# 16-BitSW.net
KiCad netlist of a schematic drawn in Altium Designer
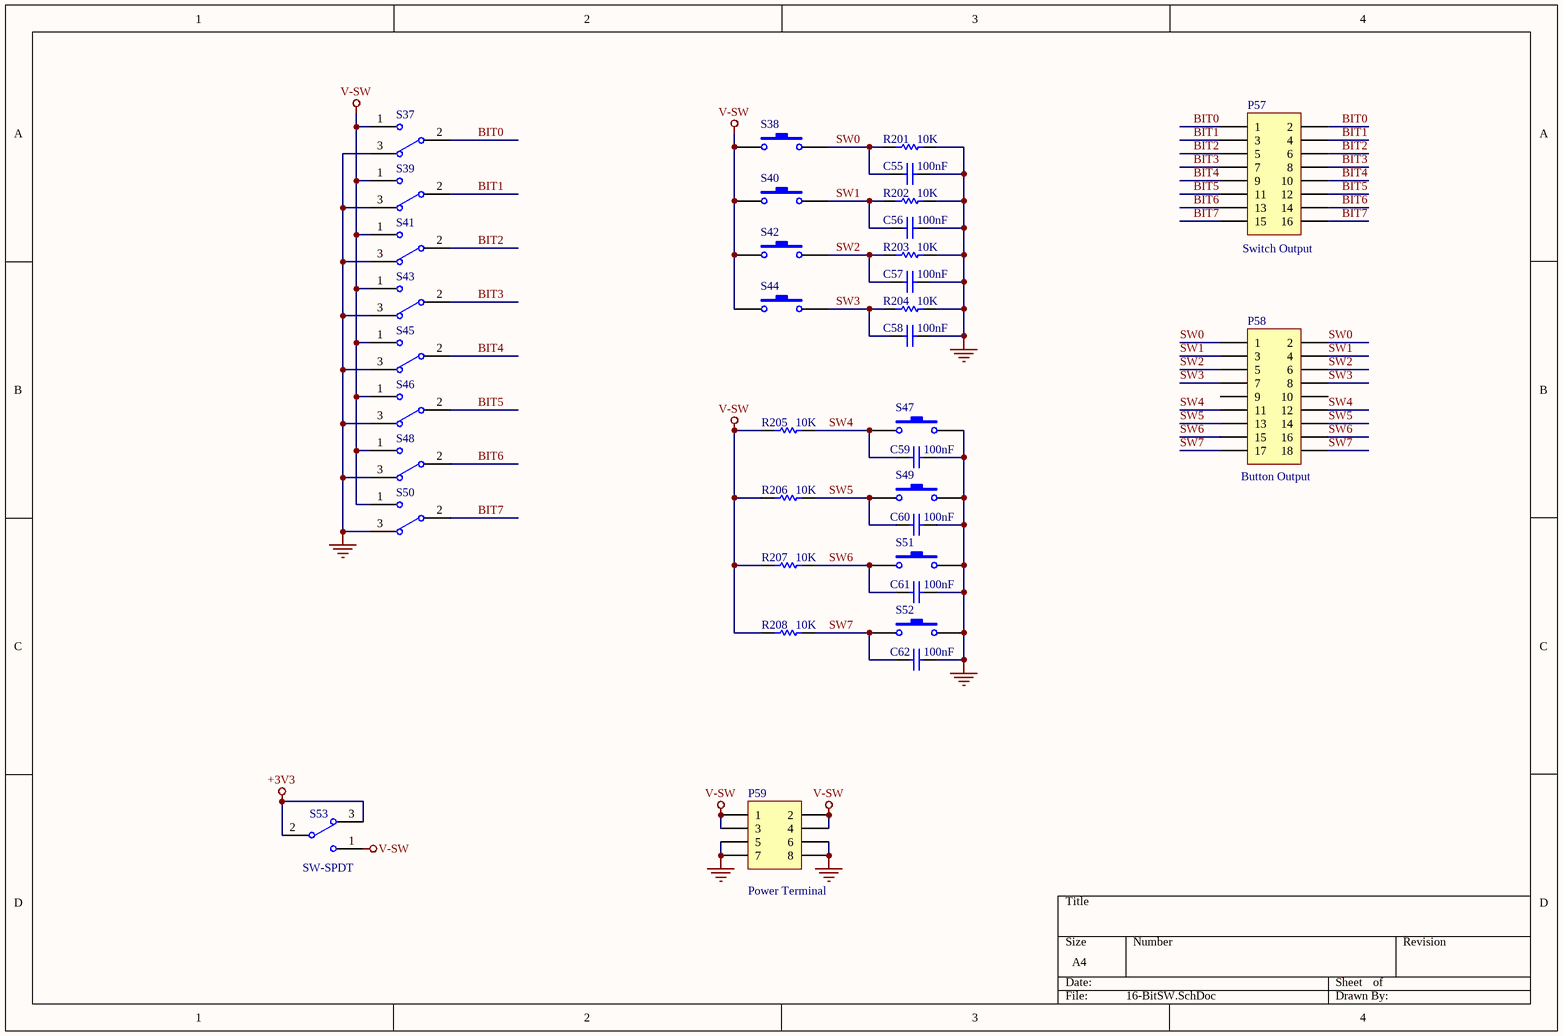
[diagram p0: 16-BitSW.SchDoc]

(export (version "E")
  (design (tool "Eeschema 10.0.6"))
  (components
    (comp (ref "C55")
      (value "100nF")
      (footprint "C-0805")
      (description "Capacitor")
      (fields
        (field (name "MANUFACTURER") "Generic Components")
        (field (name "Comment") "104")
        (field (name "PUBLISHER") "Altium Hobart Technology Centre")
      )
      (libsource (lib "Miscellaneous Devices") (part "Cap"))
    )
    (comp (ref "C56")
      (value "100nF")
      (footprint "C-0805")
      (description "Capacitor")
      (fields
        (field (name "MANUFACTURER") "Generic Components")
        (field (name "Comment") "104")
        (field (name "PUBLISHER") "Altium Hobart Technology Centre")
      )
      (libsource (lib "Miscellaneous Devices") (part "Cap"))
    )
    (comp (ref "C57")
      (value "100nF")
      (footprint "C-0805")
      (description "Capacitor")
      (fields
        (field (name "MANUFACTURER") "Generic Components")
        (field (name "Comment") "104")
        (field (name "PUBLISHER") "Altium Hobart Technology Centre")
      )
      (libsource (lib "Miscellaneous Devices") (part "Cap"))
    )
    (comp (ref "C58")
      (value "100nF")
      (footprint "C-0805")
      (description "Capacitor")
      (fields
        (field (name "MANUFACTURER") "Generic Components")
        (field (name "Comment") "104")
        (field (name "PUBLISHER") "Altium Hobart Technology Centre")
      )
      (libsource (lib "Miscellaneous Devices") (part "Cap"))
    )
    (comp (ref "C59")
      (value "100nF")
      (footprint "C-0805")
      (description "Capacitor")
      (fields
        (field (name "MANUFACTURER") "Generic Components")
        (field (name "Comment") "104")
        (field (name "PUBLISHER") "Altium Hobart Technology Centre")
      )
      (libsource (lib "Miscellaneous Devices") (part "Cap"))
    )
    (comp (ref "C60")
      (value "100nF")
      (footprint "C-0805")
      (description "Capacitor")
      (fields
        (field (name "MANUFACTURER") "Generic Components")
        (field (name "Comment") "104")
        (field (name "PUBLISHER") "Altium Hobart Technology Centre")
      )
      (libsource (lib "Miscellaneous Devices") (part "Cap"))
    )
    (comp (ref "C61")
      (value "100nF")
      (footprint "C-0805")
      (description "Capacitor")
      (fields
        (field (name "MANUFACTURER") "Generic Components")
        (field (name "Comment") "104")
        (field (name "PUBLISHER") "Altium Hobart Technology Centre")
      )
      (libsource (lib "Miscellaneous Devices") (part "Cap"))
    )
    (comp (ref "C62")
      (value "100nF")
      (footprint "C-0805")
      (description "Capacitor")
      (fields
        (field (name "MANUFACTURER") "Generic Components")
        (field (name "Comment") "104")
        (field (name "PUBLISHER") "Altium Hobart Technology Centre")
      )
      (libsource (lib "Miscellaneous Devices") (part "Cap"))
    )
    (comp (ref "P57")
      (value "Switch Output")
      (footprint "HDR2X8")
      (description "Header, 8-Pin, Dual row")
      (fields (field (name "Comment") "Header 8X2"))
      (libsource (lib "Miscellaneous Connectors") (part "Header 8X2"))
    )
    (comp (ref "P58")
      (value "Button Output")
      (footprint "HDR2X9")
      (description "Header, 9-Pin, Dual row")
      (fields (field (name "Comment") "Header 9X2"))
      (libsource (lib "Miscellaneous Connectors") (part "Header 9X2"))
    )
    (comp (ref "P59")
      (value "Header 4X2")
      (footprint "HDR2X4")
      (description "Header, 4-Pin, Dual row")
      (fields (field (name "PUBLISHER") "Power Terminal"))
      (libsource (lib "Miscellaneous Connectors") (part "Header 4X2"))
    )
    (comp (ref "R201")
      (value "10K")
      (footprint "r-0805")
      (description "Resistor")
      (fields (field (name "PUBLISHER") "Altium Limited"))
      (libsource (lib "Miscellaneous Devices") (part "Res1"))
    )
    (comp (ref "R202")
      (value "10K")
      (footprint "r-0805")
      (description "Resistor")
      (fields (field (name "PUBLISHER") "Altium Limited"))
      (libsource (lib "Miscellaneous Devices") (part "Res1"))
    )
    (comp (ref "R203")
      (value "10K")
      (footprint "r-0805")
      (description "Resistor")
      (fields (field (name "PUBLISHER") "Altium Limited"))
      (libsource (lib "Miscellaneous Devices") (part "Res1"))
    )
    (comp (ref "R204")
      (value "10K")
      (footprint "r-0805")
      (description "Resistor")
      (fields (field (name "PUBLISHER") "Altium Limited"))
      (libsource (lib "Miscellaneous Devices") (part "Res1"))
    )
    (comp (ref "R205")
      (value "10K")
      (footprint "r-0805")
      (description "Resistor")
      (fields (field (name "PUBLISHER") "Altium Limited"))
      (libsource (lib "Miscellaneous Devices") (part "Res1"))
    )
    (comp (ref "R206")
      (value "10K")
      (footprint "r-0805")
      (description "Resistor")
      (fields (field (name "PUBLISHER") "Altium Limited"))
      (libsource (lib "Miscellaneous Devices") (part "Res1"))
    )
    (comp (ref "R207")
      (value "10K")
      (footprint "r-0805")
      (description "Resistor")
      (fields (field (name "PUBLISHER") "Altium Limited"))
      (libsource (lib "Miscellaneous Devices") (part "Res1"))
    )
    (comp (ref "R208")
      (value "10K")
      (footprint "r-0805")
      (description "Resistor")
      (fields (field (name "PUBLISHER") "Altium Limited"))
      (libsource (lib "Miscellaneous Devices") (part "Res1"))
    )
    (comp (ref "S37")
      (value "SW-SPDT")
      (footprint "SW-DIP1SMD")
      (description "SPDT Subminiature Toggle Switch, Right Angle Mounting, Vertical Actuation")
      (fields (field (name "PUBLISHER") "Altium Limited"))
      (libsource (lib "Miscellaneous Devices") (part "SW-SPDT"))
    )
    (comp (ref "S38")
      (value "SW2")
      (footprint "sw2")
      (description "Switch")
      (fields (field (name "PUBLISHER") "Altium Limited"))
      (libsource (lib "Miscellaneous Devices") (part "SW-PB"))
    )
    (comp (ref "S39")
      (value "SW-SPDT")
      (footprint "SW-DIP1SMD")
      (description "SPDT Subminiature Toggle Switch, Right Angle Mounting, Vertical Actuation")
      (fields (field (name "PUBLISHER") "Altium Limited"))
      (libsource (lib "Miscellaneous Devices") (part "SW-SPDT"))
    )
    (comp (ref "S40")
      (value "SW2")
      (footprint "sw2")
      (description "Switch")
      (fields (field (name "PUBLISHER") "Altium Limited"))
      (libsource (lib "Miscellaneous Devices") (part "SW-PB"))
    )
    (comp (ref "S41")
      (value "SW-SPDT")
      (footprint "SW-DIP1SMD")
      (description "SPDT Subminiature Toggle Switch, Right Angle Mounting, Vertical Actuation")
      (fields (field (name "PUBLISHER") "Altium Limited"))
      (libsource (lib "Miscellaneous Devices") (part "SW-SPDT"))
    )
    (comp (ref "S42")
      (value "SW2")
      (footprint "sw2")
      (description "Switch")
      (fields (field (name "PUBLISHER") "Altium Limited"))
      (libsource (lib "Miscellaneous Devices") (part "SW-PB"))
    )
    (comp (ref "S43")
      (value "SW-SPDT")
      (footprint "SW-DIP1SMD")
      (description "SPDT Subminiature Toggle Switch, Right Angle Mounting, Vertical Actuation")
      (fields (field (name "PUBLISHER") "Altium Limited"))
      (libsource (lib "Miscellaneous Devices") (part "SW-SPDT"))
    )
    (comp (ref "S44")
      (value "SW2")
      (footprint "sw2")
      (description "Switch")
      (fields (field (name "PUBLISHER") "Altium Limited"))
      (libsource (lib "Miscellaneous Devices") (part "SW-PB"))
    )
    (comp (ref "S45")
      (value "SW-SPDT")
      (footprint "SW-DIP1SMD")
      (description "SPDT Subminiature Toggle Switch, Right Angle Mounting, Vertical Actuation")
      (fields (field (name "PUBLISHER") "Altium Limited"))
      (libsource (lib "Miscellaneous Devices") (part "SW-SPDT"))
    )
    (comp (ref "S46")
      (value "SW-SPDT")
      (footprint "SW-DIP1SMD")
      (description "SPDT Subminiature Toggle Switch, Right Angle Mounting, Vertical Actuation")
      (fields (field (name "PUBLISHER") "Altium Limited"))
      (libsource (lib "Miscellaneous Devices") (part "SW-SPDT"))
    )
    (comp (ref "S47")
      (value "SW2")
      (footprint "sw2")
      (description "Switch")
      (fields (field (name "PUBLISHER") "Altium Limited"))
      (libsource (lib "Miscellaneous Devices") (part "SW-PB"))
    )
    (comp (ref "S48")
      (value "SW-SPDT")
      (footprint "SW-DIP1SMD")
      (description "SPDT Subminiature Toggle Switch, Right Angle Mounting, Vertical Actuation")
      (fields (field (name "PUBLISHER") "Altium Limited"))
      (libsource (lib "Miscellaneous Devices") (part "SW-SPDT"))
    )
    (comp (ref "S49")
      (value "SW2")
      (footprint "sw2")
      (description "Switch")
      (fields (field (name "PUBLISHER") "Altium Limited"))
      (libsource (lib "Miscellaneous Devices") (part "SW-PB"))
    )
    (comp (ref "S50")
      (value "SW-SPDT")
      (footprint "SW-DIP1SMD")
      (description "SPDT Subminiature Toggle Switch, Right Angle Mounting, Vertical Actuation")
      (fields (field (name "PUBLISHER") "Altium Limited"))
      (libsource (lib "Miscellaneous Devices") (part "SW-SPDT"))
    )
    (comp (ref "S51")
      (value "SW2")
      (footprint "sw2")
      (description "Switch")
      (fields (field (name "PUBLISHER") "Altium Limited"))
      (libsource (lib "Miscellaneous Devices") (part "SW-PB"))
    )
    (comp (ref "S52")
      (value "SW2")
      (footprint "sw2")
      (description "Switch")
      (fields (field (name "PUBLISHER") "Altium Limited"))
      (libsource (lib "Miscellaneous Devices") (part "SW-PB"))
    )
    (comp (ref "S53")
      (value "SW-SPDT")
      (footprint "SW-DIP1SMD")
      (description "SPDT Subminiature Toggle Switch, Right Angle Mounting, Vertical Actuation")
      (fields (field (name "PUBLISHER") "Altium Limited"))
      (libsource (lib "Miscellaneous Devices") (part "SW-SPDT"))
    )
  )
  (nets
    (net (code "1") (name "+3V3") (class "Default")
      (node (ref "S53") (pin "2") (pinfunction "2_2") (pintype "passive"))
      (node (ref "S53") (pin "3") (pinfunction "3_3") (pintype "passive"))
    )
    (net (code "2") (name "/BIT0") (class "Default")
      (node (ref "P57") (pin "1") (pinfunction "1_1") (pintype "passive"))
      (node (ref "P57") (pin "2") (pinfunction "2_2") (pintype "passive"))
      (node (ref "S37") (pin "2") (pinfunction "2_2") (pintype "passive"))
    )
    (net (code "3") (name "/BIT1") (class "Default")
      (node (ref "P57") (pin "3") (pinfunction "3_3") (pintype "passive"))
      (node (ref "P57") (pin "4") (pinfunction "4_4") (pintype "passive"))
      (node (ref "S39") (pin "2") (pinfunction "2_2") (pintype "passive"))
    )
    (net (code "4") (name "/BIT2") (class "Default")
      (node (ref "P57") (pin "5") (pinfunction "5_5") (pintype "passive"))
      (node (ref "P57") (pin "6") (pinfunction "6_6") (pintype "passive"))
      (node (ref "S41") (pin "2") (pinfunction "2_2") (pintype "passive"))
    )
    (net (code "5") (name "/BIT3") (class "Default")
      (node (ref "P57") (pin "7") (pinfunction "7_7") (pintype "passive"))
      (node (ref "P57") (pin "8") (pinfunction "8_8") (pintype "passive"))
      (node (ref "S43") (pin "2") (pinfunction "2_2") (pintype "passive"))
    )
    (net (code "6") (name "/BIT4") (class "Default")
      (node (ref "P57") (pin "10") (pinfunction "10_10") (pintype "passive"))
      (node (ref "P57") (pin "9") (pinfunction "9_9") (pintype "passive"))
      (node (ref "S45") (pin "2") (pinfunction "2_2") (pintype "passive"))
    )
    (net (code "7") (name "/BIT5") (class "Default")
      (node (ref "P57") (pin "11") (pinfunction "11_11") (pintype "passive"))
      (node (ref "P57") (pin "12") (pinfunction "12_12") (pintype "passive"))
      (node (ref "S46") (pin "2") (pinfunction "2_2") (pintype "passive"))
    )
    (net (code "8") (name "/BIT6") (class "Default")
      (node (ref "P57") (pin "13") (pinfunction "13_13") (pintype "passive"))
      (node (ref "P57") (pin "14") (pinfunction "14_14") (pintype "passive"))
      (node (ref "S48") (pin "2") (pinfunction "2_2") (pintype "passive"))
    )
    (net (code "9") (name "/BIT7") (class "Default")
      (node (ref "P57") (pin "15") (pinfunction "15_15") (pintype "passive"))
      (node (ref "P57") (pin "16") (pinfunction "16_16") (pintype "passive"))
      (node (ref "S50") (pin "2") (pinfunction "2_2") (pintype "passive"))
    )
    (net (code "10") (name "/SW0") (class "Default")
      (node (ref "C55") (pin "2") (pinfunction "2_2") (pintype "passive"))
      (node (ref "P58") (pin "1") (pinfunction "1_1") (pintype "passive"))
      (node (ref "P58") (pin "2") (pinfunction "2_2") (pintype "passive"))
      (node (ref "R201") (pin "2") (pinfunction "2_2") (pintype "passive"))
      (node (ref "S38") (pin "2") (pinfunction "2_2") (pintype "passive"))
    )
    (net (code "11") (name "/SW1") (class "Default")
      (node (ref "C56") (pin "2") (pinfunction "2_2") (pintype "passive"))
      (node (ref "P58") (pin "3") (pinfunction "3_3") (pintype "passive"))
      (node (ref "P58") (pin "4") (pinfunction "4_4") (pintype "passive"))
      (node (ref "R202") (pin "2") (pinfunction "2_2") (pintype "passive"))
      (node (ref "S40") (pin "2") (pinfunction "2_2") (pintype "passive"))
    )
    (net (code "12") (name "/SW2") (class "Default")
      (node (ref "C57") (pin "2") (pinfunction "2_2") (pintype "passive"))
      (node (ref "P58") (pin "5") (pinfunction "5_5") (pintype "passive"))
      (node (ref "P58") (pin "6") (pinfunction "6_6") (pintype "passive"))
      (node (ref "R203") (pin "2") (pinfunction "2_2") (pintype "passive"))
      (node (ref "S42") (pin "2") (pinfunction "2_2") (pintype "passive"))
    )
    (net (code "13") (name "/SW3") (class "Default")
      (node (ref "C58") (pin "2") (pinfunction "2_2") (pintype "passive"))
      (node (ref "P58") (pin "7") (pinfunction "7_7") (pintype "passive"))
      (node (ref "P58") (pin "8") (pinfunction "8_8") (pintype "passive"))
      (node (ref "R204") (pin "2") (pinfunction "2_2") (pintype "passive"))
      (node (ref "S44") (pin "2") (pinfunction "2_2") (pintype "passive"))
    )
    (net (code "14") (name "/SW4") (class "Default")
      (node (ref "C59") (pin "2") (pinfunction "2_2") (pintype "passive"))
      (node (ref "P58") (pin "11") (pinfunction "11_11") (pintype "passive"))
      (node (ref "P58") (pin "12") (pinfunction "12_12") (pintype "passive"))
      (node (ref "R205") (pin "1") (pinfunction "1_1") (pintype "passive"))
      (node (ref "S47") (pin "1") (pinfunction "1_1") (pintype "passive"))
    )
    (net (code "15") (name "/SW5") (class "Default")
      (node (ref "C60") (pin "2") (pinfunction "2_2") (pintype "passive"))
      (node (ref "P58") (pin "13") (pinfunction "13_13") (pintype "passive"))
      (node (ref "P58") (pin "14") (pinfunction "14_14") (pintype "passive"))
      (node (ref "R206") (pin "1") (pinfunction "1_1") (pintype "passive"))
      (node (ref "S49") (pin "1") (pinfunction "1_1") (pintype "passive"))
    )
    (net (code "16") (name "/SW6") (class "Default")
      (node (ref "C61") (pin "2") (pinfunction "2_2") (pintype "passive"))
      (node (ref "P58") (pin "15") (pinfunction "15_15") (pintype "passive"))
      (node (ref "P58") (pin "16") (pinfunction "16_16") (pintype "passive"))
      (node (ref "R207") (pin "1") (pinfunction "1_1") (pintype "passive"))
      (node (ref "S51") (pin "1") (pinfunction "1_1") (pintype "passive"))
    )
    (net (code "17") (name "/SW7") (class "Default")
      (node (ref "C62") (pin "2") (pinfunction "2_2") (pintype "passive"))
      (node (ref "P58") (pin "17") (pinfunction "17_17") (pintype "passive"))
      (node (ref "P58") (pin "18") (pinfunction "18_18") (pintype "passive"))
      (node (ref "R208") (pin "1") (pinfunction "1_1") (pintype "passive"))
      (node (ref "S52") (pin "1") (pinfunction "1_1") (pintype "passive"))
    )
    (net (code "18") (name "GND") (class "Default")
      (node (ref "C55") (pin "1") (pinfunction "1_1") (pintype "passive"))
      (node (ref "C56") (pin "1") (pinfunction "1_1") (pintype "passive"))
      (node (ref "C57") (pin "1") (pinfunction "1_1") (pintype "passive"))
      (node (ref "C58") (pin "1") (pinfunction "1_1") (pintype "passive"))
      (node (ref "C59") (pin "1") (pinfunction "1_1") (pintype "passive"))
      (node (ref "C60") (pin "1") (pinfunction "1_1") (pintype "passive"))
      (node (ref "C61") (pin "1") (pinfunction "1_1") (pintype "passive"))
      (node (ref "C62") (pin "1") (pinfunction "1_1") (pintype "passive"))
      (node (ref "P59") (pin "5") (pinfunction "5_5") (pintype "passive"))
      (node (ref "P59") (pin "6") (pinfunction "6_6") (pintype "passive"))
      (node (ref "P59") (pin "7") (pinfunction "7_7") (pintype "passive"))
      (node (ref "P59") (pin "8") (pinfunction "8_8") (pintype "passive"))
      (node (ref "R201") (pin "1") (pinfunction "1_1") (pintype "passive"))
      (node (ref "R202") (pin "1") (pinfunction "1_1") (pintype "passive"))
      (node (ref "R203") (pin "1") (pinfunction "1_1") (pintype "passive"))
      (node (ref "R204") (pin "1") (pinfunction "1_1") (pintype "passive"))
      (node (ref "S37") (pin "3") (pinfunction "3_3") (pintype "passive"))
      (node (ref "S39") (pin "3") (pinfunction "3_3") (pintype "passive"))
      (node (ref "S41") (pin "3") (pinfunction "3_3") (pintype "passive"))
      (node (ref "S43") (pin "3") (pinfunction "3_3") (pintype "passive"))
      (node (ref "S45") (pin "3") (pinfunction "3_3") (pintype "passive"))
      (node (ref "S46") (pin "3") (pinfunction "3_3") (pintype "passive"))
      (node (ref "S47") (pin "2") (pinfunction "2_2") (pintype "passive"))
      (node (ref "S48") (pin "3") (pinfunction "3_3") (pintype "passive"))
      (node (ref "S49") (pin "2") (pinfunction "2_2") (pintype "passive"))
      (node (ref "S50") (pin "3") (pinfunction "3_3") (pintype "passive"))
      (node (ref "S51") (pin "2") (pinfunction "2_2") (pintype "passive"))
      (node (ref "S52") (pin "2") (pinfunction "2_2") (pintype "passive"))
    )
    (net (code "19") (name "V-SW") (class "Default")
      (node (ref "P59") (pin "1") (pinfunction "1_1") (pintype "passive"))
      (node (ref "P59") (pin "2") (pinfunction "2_2") (pintype "passive"))
      (node (ref "P59") (pin "3") (pinfunction "3_3") (pintype "passive"))
      (node (ref "P59") (pin "4") (pinfunction "4_4") (pintype "passive"))
      (node (ref "R205") (pin "2") (pinfunction "2_2") (pintype "passive"))
      (node (ref "R206") (pin "2") (pinfunction "2_2") (pintype "passive"))
      (node (ref "R207") (pin "2") (pinfunction "2_2") (pintype "passive"))
      (node (ref "R208") (pin "2") (pinfunction "2_2") (pintype "passive"))
      (node (ref "S37") (pin "1") (pinfunction "1_1") (pintype "passive"))
      (node (ref "S38") (pin "1") (pinfunction "1_1") (pintype "passive"))
      (node (ref "S39") (pin "1") (pinfunction "1_1") (pintype "passive"))
      (node (ref "S40") (pin "1") (pinfunction "1_1") (pintype "passive"))
      (node (ref "S41") (pin "1") (pinfunction "1_1") (pintype "passive"))
      (node (ref "S42") (pin "1") (pinfunction "1_1") (pintype "passive"))
      (node (ref "S43") (pin "1") (pinfunction "1_1") (pintype "passive"))
      (node (ref "S44") (pin "1") (pinfunction "1_1") (pintype "passive"))
      (node (ref "S45") (pin "1") (pinfunction "1_1") (pintype "passive"))
      (node (ref "S46") (pin "1") (pinfunction "1_1") (pintype "passive"))
      (node (ref "S48") (pin "1") (pinfunction "1_1") (pintype "passive"))
      (node (ref "S50") (pin "1") (pinfunction "1_1") (pintype "passive"))
      (node (ref "S53") (pin "1") (pinfunction "1_1") (pintype "passive"))
    )
    (net (code "20") (name "unconnected-(P58-Pad9)") (class "Default")
      (node (ref "P58") (pin "9") (pinfunction "9_9") (pintype "passive"))
    )
    (net (code "21") (name "unconnected-(P58-Pad10)") (class "Default")
      (node (ref "P58") (pin "10") (pinfunction "10_10") (pintype "passive"))
    )
  )
)
